# adc.net
KiCad netlist of a schematic drawn in Altium Designer
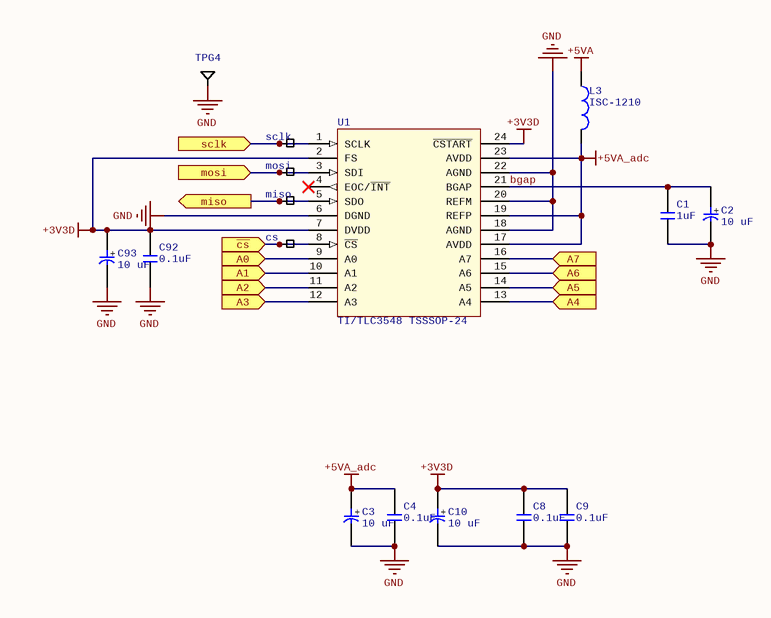
[diagram p0: adc.SchDoc]

(export (version "E")
  (design (tool "Eeschema 10.0.6"))
  (components
    (comp (ref "C1")
      (value "1uF")
      (footprint "C0603")
      (description "CAP2, CER, 1.0uF, 10%, 25V, 0603")
      (fields
        (field (name "MANUFACTURER") "Murata Electronics North America")
        (field (name "MANUFACTURER PART NUMBER") "GRM188R61E105KA12D")
      )
      (libsource (lib "stdlib") (part "Murata/GRM188R61E105KA12D"))
    )
    (comp (ref "C2")
      (value "10 uF")
      (footprint "KEMET 1206")
      (description "CAP2, TANT,  10uF, 10%, 10V, 1206")
      (fields
        (field (name "MANUFACTURER") "Kemet")
        (field (name "MANUFACTURER PART NUMBER") "T491A106K010AT")
      )
      (libsource (lib "stdlib") (part "Kemet/T491A106K010AT"))
    )
    (comp (ref "C3")
      (value "10 uF")
      (footprint "KEMET 1206")
      (description "CAP2, TANT,  10uF, 10%, 10V, 1206")
      (fields
        (field (name "MANUFACTURER") "Kemet")
        (field (name "MANUFACTURER PART NUMBER") "T491A106K010AT")
      )
      (libsource (lib "stdlib") (part "Kemet/T491A106K010AT"))
    )
    (comp (ref "C4")
      (value "0.1uF")
      (footprint "C0603")
      (description "CAP2, CER, 0.1uF, 10%, 50V, 0603, X7R")
      (fields
        (field (name "MANUFACTURER") "AVX Corporation")
        (field (name "MANUFACTURER PART NUMBER") "06035C104KAT2A")
      )
      (libsource (lib "stdlib") (part "CAP/06035C104KAT2A"))
    )
    (comp (ref "C8")
      (value "0.1uF")
      (footprint "C0603")
      (description "CAP2, CER, 0.1uF, 10%, 50V, 0603, X7R")
      (fields
        (field (name "MANUFACTURER") "AVX Corporation")
        (field (name "MANUFACTURER PART NUMBER") "06035C104KAT2A")
      )
      (libsource (lib "stdlib") (part "CAP/06035C104KAT2A"))
    )
    (comp (ref "C9")
      (value "0.1uF")
      (footprint "C0603")
      (description "CAP2, CER, 0.1uF, 10%, 50V, 0603, X7R")
      (fields
        (field (name "MANUFACTURER") "AVX Corporation")
        (field (name "MANUFACTURER PART NUMBER") "06035C104KAT2A")
      )
      (libsource (lib "stdlib") (part "CAP/06035C104KAT2A"))
    )
    (comp (ref "C10")
      (value "10 uF")
      (footprint "KEMET 1206")
      (description "CAP2, TANT,  10uF, 10%, 10V, 1206")
      (fields
        (field (name "MANUFACTURER") "Kemet")
        (field (name "MANUFACTURER PART NUMBER") "T491A106K010AT")
      )
      (libsource (lib "stdlib") (part "Kemet/T491A106K010AT"))
    )
    (comp (ref "C92")
      (value "0.1uF")
      (footprint "C0603")
      (description "CAP2, CER, 0.1uF, 10%, 50V, 0603, X7R")
      (fields
        (field (name "MANUFACTURER") "AVX Corporation")
        (field (name "MANUFACTURER PART NUMBER") "06035C104KAT2A")
      )
      (libsource (lib "stdlib") (part "CAP/06035C104KAT2A"))
    )
    (comp (ref "C93")
      (value "10 uF")
      (footprint "KEMET 1206")
      (description "CAP2, TANT,  10uF, 10%, 10V, 1206")
      (fields
        (field (name "MANUFACTURER") "Kemet")
        (field (name "MANUFACTURER PART NUMBER") "T491A106K010AT")
      )
      (libsource (lib "stdlib") (part "Kemet/T491A106K010AT"))
    )
    (comp (ref "cs")
      (value "TP_SMALL")
      (footprint "TP_SMALL")
      (description "Test Point, Generic, 50MIL")
      (libsource (lib "stdlib") (part "TP_SMALL"))
    )
    (comp (ref "L3")
      (value "ISC-1210")
      (footprint "ISC-1210")
      (description "IND, 86uF, 90mA")
      (libsource (lib "stdlib") (part "ISC-1210"))
    )
    (comp (ref "miso")
      (value "TP_SMALL")
      (footprint "TP_SMALL")
      (description "Test Point, Generic, 50MIL")
      (libsource (lib "stdlib") (part "TP_SMALL"))
    )
    (comp (ref "mosi")
      (value "TP_SMALL")
      (footprint "TP_SMALL")
      (description "Test Point, Generic, 50MIL")
      (libsource (lib "stdlib") (part "TP_SMALL"))
    )
    (comp (ref "sclk")
      (value "TP_SMALL")
      (footprint "TP_SMALL")
      (description "Test Point, Generic, 50MIL")
      (libsource (lib "stdlib") (part "TP_SMALL"))
    )
    (comp (ref "TPG4")
      (value "TPG")
      (footprint "TPG")
      (description "Test Point, GND, Through Hole")
      (libsource (lib "stdlib") (part "TPG"))
    )
    (comp (ref "U1")
      (value "TI/TLC3548 TSSSOP-24")
      (footprint "TSSOP-24")
      (description "ADC, 14-Bit,")
      (fields
        (field (name "MANUFACTURER") "Texas Instruments")
        (field (name "MANUFACTURER PART NUMBER") "TLC3548CPW")
      )
      (libsource (lib "stdlib") (part "TI/TLC3548 TSSSOP-24"))
    )
  )
  (nets
    (net (code "1") (name "+3V3D") (class "Default")
      (node (ref "C10") (pin "1") (pinfunction "+_1") (pintype "passive"))
      (node (ref "C8") (pin "2") (pinfunction "2_2") (pintype "passive"))
      (node (ref "C9") (pin "2") (pinfunction "2_2") (pintype "passive"))
      (node (ref "C92") (pin "2") (pinfunction "2_2") (pintype "passive"))
      (node (ref "C93") (pin "1") (pinfunction "+_1") (pintype "passive"))
      (node (ref "U1") (pin "2") (pinfunction "FS_2") (pintype "passive"))
      (node (ref "U1") (pin "24") (pinfunction "~{CSTART}_24") (pintype "passive"))
      (node (ref "U1") (pin "7") (pinfunction "DVDD_7") (pintype "passive"))
    )
    (net (code "2") (name "+5VA") (class "Default") (node (ref "L3") (pin "2") (pintype "passive")))
    (net (code "3") (name "+5VA_adc") (class "Default")
      (node (ref "C3") (pin "1") (pinfunction "+_1") (pintype "passive"))
      (node (ref "C4") (pin "2") (pinfunction "2_2") (pintype "passive"))
      (node (ref "L3") (pin "1") (pintype "passive"))
      (node (ref "U1") (pin "17") (pinfunction "AVDD_17") (pintype "passive"))
      (node (ref "U1") (pin "19") (pinfunction "REFP_19") (pintype "passive"))
      (node (ref "U1") (pin "23") (pinfunction "AVDD_23") (pintype "passive"))
    )
    (net (code "4") (name "/A0") (class "Default")
      (node (ref "U1") (pin "9") (pinfunction "A0_9") (pintype "passive"))
    )
    (net (code "5") (name "/A1") (class "Default")
      (node (ref "U1") (pin "10") (pinfunction "A1_10") (pintype "passive"))
    )
    (net (code "6") (name "/A2") (class "Default")
      (node (ref "U1") (pin "11") (pinfunction "A2_11") (pintype "passive"))
    )
    (net (code "7") (name "/A3") (class "Default")
      (node (ref "U1") (pin "12") (pinfunction "A3_12") (pintype "passive"))
    )
    (net (code "8") (name "/A4") (class "Default")
      (node (ref "U1") (pin "13") (pinfunction "A4_13") (pintype "passive"))
    )
    (net (code "9") (name "/A5") (class "Default")
      (node (ref "U1") (pin "14") (pinfunction "A5_14") (pintype "passive"))
    )
    (net (code "10") (name "/A6") (class "Default")
      (node (ref "U1") (pin "15") (pinfunction "A6_15") (pintype "passive"))
    )
    (net (code "11") (name "/A7") (class "Default")
      (node (ref "U1") (pin "16") (pinfunction "A7_16") (pintype "passive"))
    )
    (net (code "12") (name "/bgap") (class "Default")
      (node (ref "C1") (pin "1") (pinfunction "5_1") (pintype "passive"))
      (node (ref "C2") (pin "1") (pinfunction "+_1") (pintype "passive"))
      (node (ref "U1") (pin "21") (pinfunction "BGAP_21") (pintype "passive"))
    )
    (net (code "13") (name "/miso") (class "Default")
      (node (ref "U1") (pin "5") (pinfunction "SDO_5") (pintype "input"))
      (node (ref "miso") (pin "1") (pinfunction "1_1") (pintype "passive"))
    )
    (net (code "14") (name "/mosi") (class "Default")
      (node (ref "U1") (pin "3") (pinfunction "SDI_3") (pintype "input"))
      (node (ref "mosi") (pin "1") (pinfunction "1_1") (pintype "passive"))
    )
    (net (code "15") (name "/sclk") (class "Default")
      (node (ref "U1") (pin "1") (pinfunction "SCLK_1") (pintype "input"))
      (node (ref "sclk") (pin "1") (pinfunction "1_1") (pintype "passive"))
    )
    (net (code "16") (name "/~{cs}") (class "Default")
      (node (ref "U1") (pin "8") (pinfunction "~{CS}_8") (pintype "input"))
      (node (ref "cs") (pin "1") (pinfunction "1_1") (pintype "passive"))
    )
    (net (code "17") (name "GND") (class "Default")
      (node (ref "C1") (pin "2") (pinfunction "2_2") (pintype "passive"))
      (node (ref "C10") (pin "2") (pinfunction "-_2") (pintype "passive"))
      (node (ref "C2") (pin "2") (pinfunction "-_2") (pintype "passive"))
      (node (ref "C3") (pin "2") (pinfunction "-_2") (pintype "passive"))
      (node (ref "C4") (pin "1") (pinfunction "5_1") (pintype "passive"))
      (node (ref "C8") (pin "1") (pinfunction "5_1") (pintype "passive"))
      (node (ref "C9") (pin "1") (pinfunction "5_1") (pintype "passive"))
      (node (ref "C92") (pin "1") (pinfunction "5_1") (pintype "passive"))
      (node (ref "C93") (pin "2") (pinfunction "-_2") (pintype "passive"))
      (node (ref "TPG4") (pin "1") (pinfunction "1_1") (pintype "passive"))
      (node (ref "U1") (pin "18") (pinfunction "AGND_18") (pintype "passive"))
      (node (ref "U1") (pin "20") (pinfunction "REFM_20") (pintype "passive"))
      (node (ref "U1") (pin "22") (pinfunction "AGND_22") (pintype "passive"))
      (node (ref "U1") (pin "6") (pinfunction "DGND_6") (pintype "passive"))
    )
    (net (code "18") (name "unconnected-(U1-EOC{slash}~{INT}-Pad4)") (class "Default")
      (node (ref "U1") (pin "4") (pinfunction "EOC/~{INT}_4") (pintype "output+no_connect"))
    )
  )
)
